# 04_FAN_DRIVER.net
KiCad netlist of a schematic drawn in Altium Designer
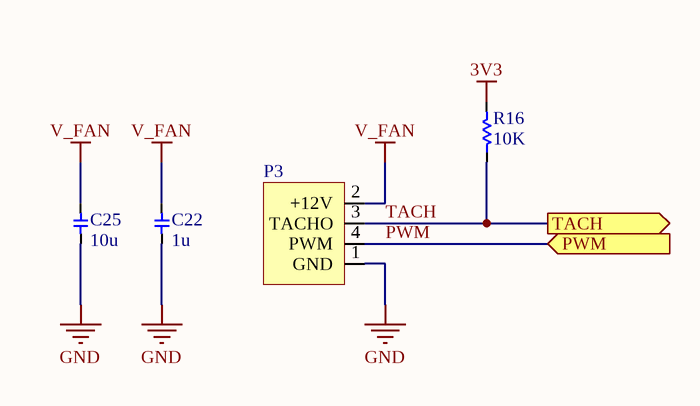
[diagram p0: 04_FAN_DRIVER.SchDoc]

(export (version "E")
  (design (tool "Eeschema 10.0.6"))
  (components
    (comp (ref "C22")
      (value "1u")
      (footprint "Footprint_Misc:0603 - CAP")
      (description "Capacitor")
      (fields
        (field (name "MANUFACTURER") "YAGEO")
        (field (name "MANUFACTURER PART NUMBER") "CC0603KRX7R9BB105")
      )
      (libsource (lib "Schematic_Misc") (part "Cap"))
    )
    (comp (ref "C25")
      (value "10u")
      (footprint "Footprint_Misc:0805")
      (description "Capacitor")
      (fields
        (field (name "MANUFACTURER") "Samsung Electro-Mechanics")
        (field (name "MANUFACTURER PART NUMBER") "CL21B106KOQNNNE")
      )
      (libsource (lib "Schematic_Misc") (part "Cap"))
    )
    (comp (ref "P3")
      (value "WM4330-ND")
      (footprint "FAN_Connector_4pin")
      (description "4 Positions Header Connector 0.100\" (2.54mm) Through Hole Tin")
      (fields (field (name "MANUFACTURER") "Molex") (field (name "DISTRIBUTOR PART NUMBER") "C3025061"))
      (libsource (lib "Schematic_Misc") (part "Header 4-pin Intel Fan"))
    )
    (comp (ref "R16")
      (value "10K")
      (footprint "Footprint_Misc:0402")
      (description "Resistor")
      (fields (field (name "DISTRIBUTOR PART NUMBER") "C60490") (field (name "MANUFACTURER") "YAGEO"))
      (libsource (lib "Schematic_Misc") (part "Res"))
    )
  )
  (nets
    (net (code "1") (name "/PWM") (class "Default")
      (node (ref "P3") (pin "4") (pinfunction "PWM_4") (pintype "passive"))
    )
    (net (code "2") (name "/TACH") (class "Default")
      (node (ref "P3") (pin "3") (pinfunction "TACHO_3") (pintype "passive"))
      (node (ref "R16") (pin "1") (pinfunction "1_1") (pintype "passive"))
    )
    (net (code "3") (name "3V3") (class "Default")
      (node (ref "R16") (pin "2") (pinfunction "2_2") (pintype "passive"))
    )
    (net (code "4") (name "GND") (class "Default")
      (node (ref "C22") (pin "1") (pinfunction "1_1") (pintype "passive"))
      (node (ref "C25") (pin "1") (pinfunction "1_1") (pintype "passive"))
      (node (ref "P3") (pin "1") (pinfunction "GND_1") (pintype "passive"))
    )
    (net (code "5") (name "V_FAN") (class "Default")
      (node (ref "C22") (pin "2") (pinfunction "2_2") (pintype "passive"))
      (node (ref "C25") (pin "2") (pinfunction "2_2") (pintype "passive"))
      (node (ref "P3") (pin "2") (pinfunction "+12V_2") (pintype "passive"))
    )
  )
)
